# ultrasonic_rx.net
KiCad netlist of a schematic drawn in Altium Designer
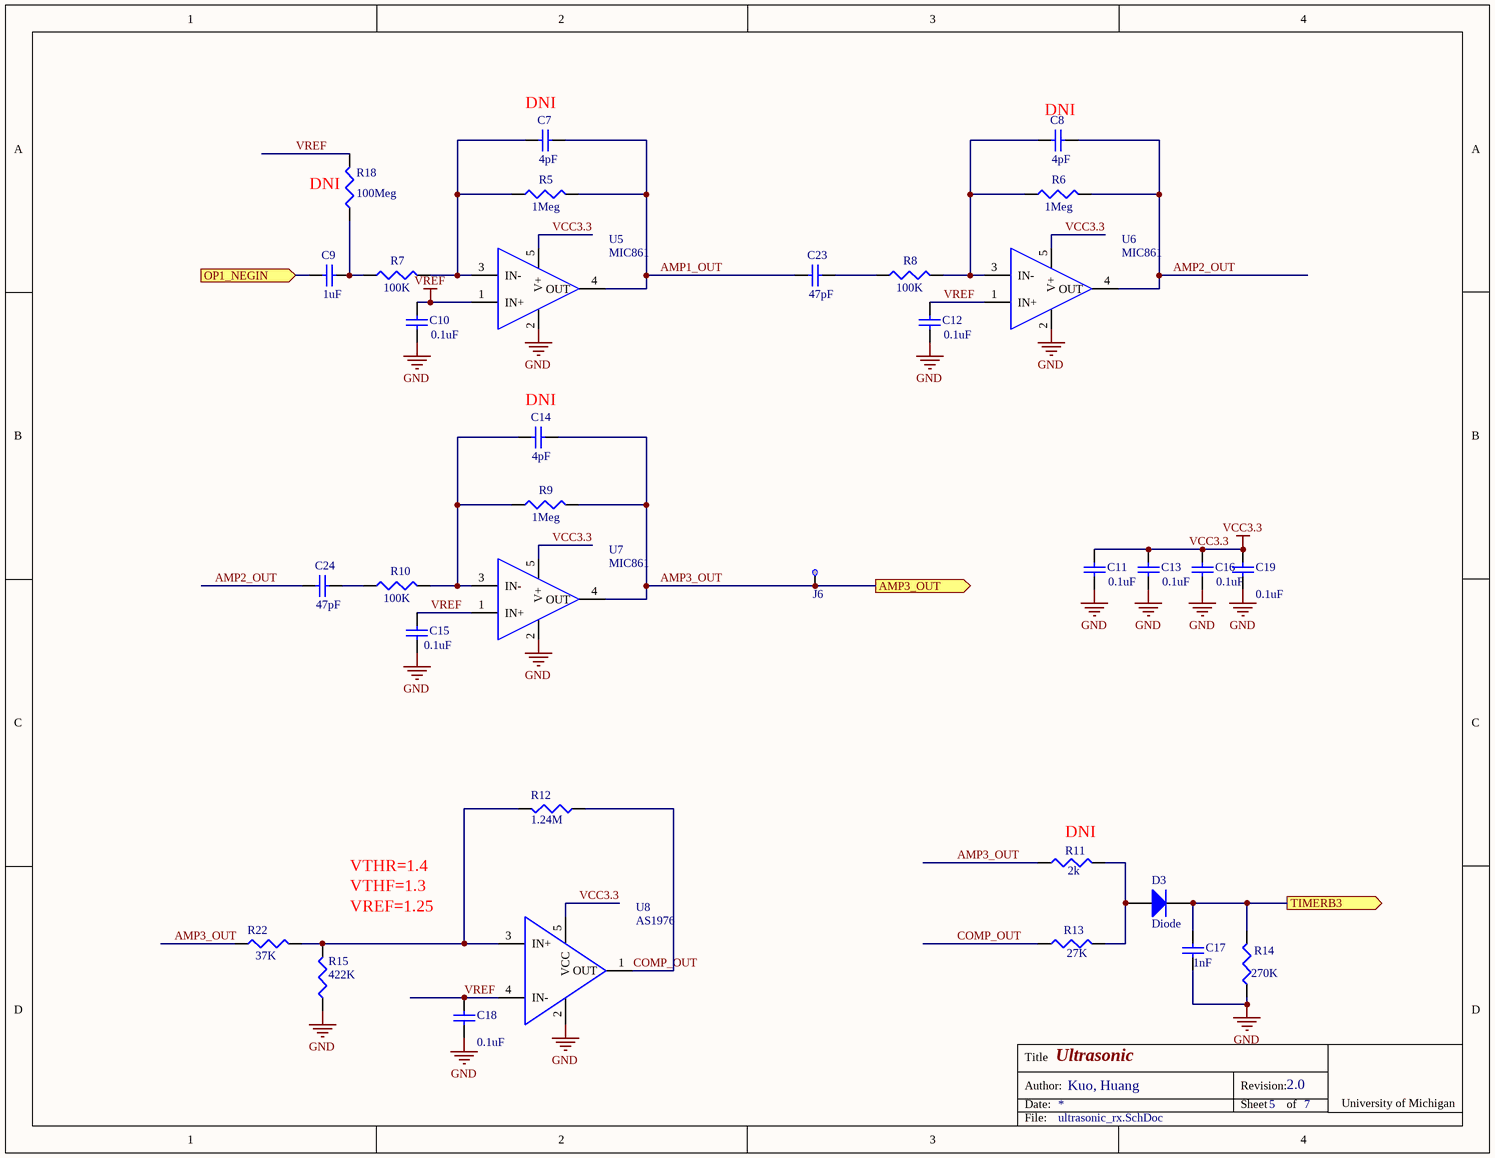
[diagram p0: ultrasonic_rx.SchDoc]

(export (version "E")
  (design (tool "Eeschema 10.0.6"))
  (components
    (comp (ref "C7")
      (value "4pF")
      (footprint "1608[0603]")
      (description "Capacitor (Semiconductor SIM Model)")
      (fields (field (name "Comment") "Cap Semi") (field (name "PUBLISHER") "Altium Limited"))
      (libsource (lib "Miscellaneous Devices") (part "Cap Semi"))
    )
    (comp (ref "C8")
      (value "4pF")
      (footprint "1608[0603]")
      (description "Capacitor (Semiconductor SIM Model)")
      (fields (field (name "Comment") "Cap Semi") (field (name "PUBLISHER") "Altium Limited"))
      (libsource (lib "Miscellaneous Devices") (part "Cap Semi"))
    )
    (comp (ref "C9")
      (value "1uF")
      (footprint "1608[0603]")
      (description "Capacitor (Semiconductor SIM Model)")
      (fields (field (name "Comment") "Cap Semi") (field (name "PUBLISHER") "Altium Limited"))
      (libsource (lib "Miscellaneous Devices") (part "Cap Semi"))
    )
    (comp (ref "C10")
      (value "0.1uF")
      (footprint "1608[0603]")
      (description "Capacitor (Semiconductor SIM Model)")
      (fields (field (name "Comment") "Cap Semi") (field (name "PUBLISHER") "Altium Limited"))
      (libsource (lib "Miscellaneous Devices") (part "Cap Semi"))
    )
    (comp (ref "C11")
      (value "0.1uF")
      (footprint "1608[0603]")
      (description "Capacitor (Semiconductor SIM Model)")
      (fields (field (name "Comment") "Cap Semi") (field (name "PUBLISHER") "Altium Limited"))
      (libsource (lib "Miscellaneous Devices") (part "Cap Semi"))
    )
    (comp (ref "C12")
      (value "0.1uF")
      (footprint "1608[0603]")
      (description "Capacitor (Semiconductor SIM Model)")
      (fields (field (name "Comment") "Cap Semi") (field (name "PUBLISHER") "Altium Limited"))
      (libsource (lib "Miscellaneous Devices") (part "Cap Semi"))
    )
    (comp (ref "C13")
      (value "0.1uF")
      (footprint "1608[0603]")
      (description "Capacitor (Semiconductor SIM Model)")
      (fields (field (name "Comment") "Cap Semi") (field (name "PUBLISHER") "Altium Limited"))
      (libsource (lib "Miscellaneous Devices") (part "Cap Semi"))
    )
    (comp (ref "C14")
      (value "4pF")
      (footprint "1608[0603]")
      (description "Capacitor (Semiconductor SIM Model)")
      (fields (field (name "Comment") "Cap Semi") (field (name "PUBLISHER") "Altium Limited"))
      (libsource (lib "Miscellaneous Devices") (part "Cap Semi"))
    )
    (comp (ref "C15")
      (value "0.1uF")
      (footprint "1608[0603]")
      (description "Capacitor (Semiconductor SIM Model)")
      (fields (field (name "Comment") "Cap Semi") (field (name "PUBLISHER") "Altium Limited"))
      (libsource (lib "Miscellaneous Devices") (part "Cap Semi"))
    )
    (comp (ref "C16")
      (value "0.1uF")
      (footprint "1608[0603]")
      (description "Capacitor (Semiconductor SIM Model)")
      (fields (field (name "Comment") "Cap Semi") (field (name "PUBLISHER") "Altium Limited"))
      (libsource (lib "Miscellaneous Devices") (part "Cap Semi"))
    )
    (comp (ref "C17")
      (value "1nF")
      (footprint "1608[0603]")
      (description "Capacitor (Semiconductor SIM Model)")
      (fields (field (name "Comment") "Cap Semi") (field (name "PUBLISHER") "Altium Limited"))
      (libsource (lib "Miscellaneous Devices") (part "Cap Semi"))
    )
    (comp (ref "C18")
      (value "0.1uF")
      (footprint "1608[0603]")
      (description "Capacitor (Semiconductor SIM Model)")
      (fields (field (name "Comment") "Cap Semi") (field (name "PUBLISHER") "Altium Limited"))
      (libsource (lib "Miscellaneous Devices") (part "Cap Semi"))
    )
    (comp (ref "C19")
      (value "0.1uF")
      (footprint "1608[0603]")
      (description "Capacitor (Semiconductor SIM Model)")
      (fields (field (name "Comment") "Cap Semi") (field (name "PUBLISHER") "Altium Limited"))
      (libsource (lib "Miscellaneous Devices") (part "Cap Semi"))
    )
    (comp (ref "C23")
      (value "47pF")
      (footprint "1608[0603]")
      (description "Capacitor (Semiconductor SIM Model)")
      (fields (field (name "Comment") "Cap Semi") (field (name "PUBLISHER") "Altium Limited"))
      (libsource (lib "Miscellaneous Devices") (part "Cap Semi"))
    )
    (comp (ref "C24")
      (value "47pF")
      (footprint "1608[0603]")
      (description "Capacitor (Semiconductor SIM Model)")
      (fields (field (name "Comment") "Cap Semi") (field (name "PUBLISHER") "Altium Limited"))
      (libsource (lib "Miscellaneous Devices") (part "Cap Semi"))
    )
    (comp (ref "D3")
      (value "Diode")
      (footprint "J1-0603")
      (description "Default Diode")
      (fields (field (name "PUBLISHER") "Altium Limited"))
      (libsource (lib "Miscellaneous Devices") (part "Diode"))
    )
    (comp (ref "J6")
      (value "5004")
      (footprint "TestPoint")
      (description "TEST POINT PC MINI .040\"D YELLOW")
      (libsource (lib "ultrasounic") (part "TestPoint"))
    )
    (comp (ref "R5")
      (value "1Meg")
      (footprint "J1-0603")
      (description "Resistor")
      (fields (field (name "PUBLISHER") "Altium Limited"))
      (libsource (lib "Miscellaneous Devices") (part "Res3"))
    )
    (comp (ref "R6")
      (value "1Meg")
      (footprint "J1-0603")
      (description "Resistor")
      (fields (field (name "PUBLISHER") "Altium Limited"))
      (libsource (lib "Miscellaneous Devices") (part "Res3"))
    )
    (comp (ref "R7")
      (value "100K")
      (footprint "J1-0603")
      (description "Resistor")
      (fields (field (name "PUBLISHER") "Altium Limited"))
      (libsource (lib "Miscellaneous Devices") (part "Res3"))
    )
    (comp (ref "R8")
      (value "100K")
      (footprint "J1-0603")
      (description "Resistor")
      (fields (field (name "PUBLISHER") "Altium Limited"))
      (libsource (lib "Miscellaneous Devices") (part "Res3"))
    )
    (comp (ref "R9")
      (value "1Meg")
      (footprint "J1-0603")
      (description "Resistor")
      (fields (field (name "PUBLISHER") "Altium Limited"))
      (libsource (lib "Miscellaneous Devices") (part "Res3"))
    )
    (comp (ref "R10")
      (value "100K")
      (footprint "J1-0603")
      (description "Resistor")
      (fields (field (name "PUBLISHER") "Altium Limited"))
      (libsource (lib "Miscellaneous Devices") (part "Res3"))
    )
    (comp (ref "R11")
      (value "2k")
      (footprint "J1-0603")
      (description "Resistor")
      (fields (field (name "PUBLISHER") "Altium Limited"))
      (libsource (lib "Miscellaneous Devices") (part "Res3"))
    )
    (comp (ref "R12")
      (value "1.24M")
      (footprint "J1-0603")
      (description "Resistor")
      (fields (field (name "PUBLISHER") "Altium Limited"))
      (libsource (lib "Miscellaneous Devices") (part "Res3"))
    )
    (comp (ref "R13")
      (value "27K")
      (footprint "J1-0603")
      (description "Resistor")
      (fields (field (name "PUBLISHER") "Altium Limited"))
      (libsource (lib "Miscellaneous Devices") (part "Res3"))
    )
    (comp (ref "R14")
      (value "270K")
      (footprint "J1-0603")
      (description "Resistor")
      (fields (field (name "PUBLISHER") "Altium Limited"))
      (libsource (lib "Miscellaneous Devices") (part "Res3"))
    )
    (comp (ref "R15")
      (value "422K")
      (footprint "J1-0603")
      (description "Resistor")
      (fields (field (name "PUBLISHER") "Altium Limited"))
      (libsource (lib "Miscellaneous Devices") (part "Res3"))
    )
    (comp (ref "R18")
      (value "100Meg")
      (footprint "J1-0603")
      (description "Resistor")
      (fields (field (name "Comment") "Res3") (field (name "PUBLISHER") "Altium Limited"))
      (libsource (lib "Miscellaneous Devices") (part "Res3"))
    )
    (comp (ref "R22")
      (value "37K")
      (footprint "J1-0603")
      (description "Resistor")
      (fields (field (name "Comment") "27K") (field (name "PUBLISHER") "Altium Limited"))
      (libsource (lib "Miscellaneous Devices") (part "Res3"))
    )
    (comp (ref "U5")
      (value "MIC861")
      (footprint "SC70-5")
      (description "IC OPAMP 400KHZ 2.7V ULT LP SC70")
      (libsource (lib "ultrasounic") (part "MIC861"))
    )
    (comp (ref "U6")
      (value "MIC861")
      (footprint "SC70-5")
      (description "IC OPAMP 400KHZ 2.7V ULT LP SC70")
      (libsource (lib "ultrasounic") (part "MIC861"))
    )
    (comp (ref "U7")
      (value "MIC861")
      (footprint "SC70-5")
      (description "IC OPAMP 400KHZ 2.7V ULT LP SC70")
      (libsource (lib "ultrasounic") (part "MIC861"))
    )
    (comp (ref "U8")
      (value "AS1976")
      (footprint "SOT23-5")
      (description "IC COMPARATOR PUSH/PULL SOT23-5")
      (libsource (lib "ultrasounic") (part "AS1976"))
    )
  )
  (nets
    (net (code "1") (name "/AMP1_OUT") (class "Default")
      (node (ref "C23") (pin "1") (pinfunction "1_1") (pintype "passive"))
      (node (ref "C7") (pin "1") (pinfunction "1_1") (pintype "passive"))
      (node (ref "R5") (pin "2") (pinfunction "2_2") (pintype "passive"))
      (node (ref "U5") (pin "4") (pinfunction "OUT_4") (pintype "passive"))
    )
    (net (code "2") (name "/AMP2_OUT") (class "Default")
      (node (ref "C24") (pin "1") (pinfunction "1_1") (pintype "passive"))
      (node (ref "C8") (pin "1") (pinfunction "1_1") (pintype "passive"))
      (node (ref "R6") (pin "2") (pinfunction "2_2") (pintype "passive"))
      (node (ref "U6") (pin "4") (pinfunction "OUT_4") (pintype "passive"))
    )
    (net (code "3") (name "/AMP3_OUT") (class "Default")
      (node (ref "C14") (pin "1") (pinfunction "1_1") (pintype "passive"))
      (node (ref "J6") (pin "1") (pinfunction "TB_1") (pintype "passive"))
      (node (ref "R11") (pin "1") (pinfunction "1_1") (pintype "passive"))
      (node (ref "R22") (pin "1") (pinfunction "1_1") (pintype "passive"))
      (node (ref "R9") (pin "2") (pinfunction "2_2") (pintype "passive"))
      (node (ref "U7") (pin "4") (pinfunction "OUT_4") (pintype "passive"))
    )
    (net (code "4") (name "/COMP_OUT") (class "Default")
      (node (ref "R12") (pin "1") (pinfunction "1_1") (pintype "passive"))
      (node (ref "R13") (pin "1") (pinfunction "1_1") (pintype "passive"))
      (node (ref "U8") (pin "1") (pinfunction "OUT_1") (pintype "passive"))
    )
    (net (code "5") (name "/OP1_NEGIN") (class "Default")
      (node (ref "C9") (pin "2") (pinfunction "2_2") (pintype "passive"))
    )
    (net (code "6") (name "/TIMERB3") (class "Default")
      (node (ref "C17") (pin "1") (pinfunction "1_1") (pintype "passive"))
      (node (ref "D3") (pin "2") (pinfunction "K_2") (pintype "passive"))
      (node (ref "R14") (pin "2") (pinfunction "2_2") (pintype "passive"))
    )
    (net (code "7") (name "GND") (class "Default")
      (node (ref "C10") (pin "1") (pinfunction "1_1") (pintype "passive"))
      (node (ref "C11") (pin "1") (pinfunction "1_1") (pintype "passive"))
      (node (ref "C12") (pin "1") (pinfunction "1_1") (pintype "passive"))
      (node (ref "C13") (pin "1") (pinfunction "1_1") (pintype "passive"))
      (node (ref "C15") (pin "1") (pinfunction "1_1") (pintype "passive"))
      (node (ref "C16") (pin "1") (pinfunction "1_1") (pintype "passive"))
      (node (ref "C17") (pin "2") (pinfunction "2_2") (pintype "passive"))
      (node (ref "C18") (pin "1") (pinfunction "1_1") (pintype "passive"))
      (node (ref "C19") (pin "1") (pinfunction "1_1") (pintype "passive"))
      (node (ref "R14") (pin "1") (pinfunction "1_1") (pintype "passive"))
      (node (ref "R15") (pin "1") (pinfunction "1_1") (pintype "passive"))
      (node (ref "U5") (pin "2") (pinfunction "V-_2") (pintype "passive"))
      (node (ref "U6") (pin "2") (pinfunction "V-_2") (pintype "passive"))
      (node (ref "U7") (pin "2") (pinfunction "V-_2") (pintype "passive"))
      (node (ref "U8") (pin "2") (pinfunction "VEE_2") (pintype "passive"))
    )
    (net (code "8") (name "Net-(C9-Pad1)") (class "Default")
      (node (ref "C9") (pin "1") (pinfunction "1_1") (pintype "passive"))
      (node (ref "R18") (pin "1") (pinfunction "1_1") (pintype "passive"))
      (node (ref "R7") (pin "1") (pinfunction "1_1") (pintype "passive"))
    )
    (net (code "9") (name "Net-(C23-Pad2)") (class "Default")
      (node (ref "C23") (pin "2") (pinfunction "2_2") (pintype "passive"))
      (node (ref "R8") (pin "1") (pinfunction "1_1") (pintype "passive"))
    )
    (net (code "10") (name "Net-(C24-Pad2)") (class "Default")
      (node (ref "C24") (pin "2") (pinfunction "2_2") (pintype "passive"))
      (node (ref "R10") (pin "1") (pinfunction "1_1") (pintype "passive"))
    )
    (net (code "11") (name "Net-(D3-A)") (class "Default")
      (node (ref "D3") (pin "1") (pinfunction "A_1") (pintype "passive"))
      (node (ref "R11") (pin "2") (pinfunction "2_2") (pintype "passive"))
      (node (ref "R13") (pin "2") (pinfunction "2_2") (pintype "passive"))
    )
    (net (code "12") (name "Net-(U5-IN-)") (class "Default")
      (node (ref "C7") (pin "2") (pinfunction "2_2") (pintype "passive"))
      (node (ref "R5") (pin "1") (pinfunction "1_1") (pintype "passive"))
      (node (ref "R7") (pin "2") (pinfunction "2_2") (pintype "passive"))
      (node (ref "U5") (pin "3") (pinfunction "IN-_3") (pintype "passive"))
    )
    (net (code "13") (name "Net-(U6-IN-)") (class "Default")
      (node (ref "C8") (pin "2") (pinfunction "2_2") (pintype "passive"))
      (node (ref "R6") (pin "1") (pinfunction "1_1") (pintype "passive"))
      (node (ref "R8") (pin "2") (pinfunction "2_2") (pintype "passive"))
      (node (ref "U6") (pin "3") (pinfunction "IN-_3") (pintype "passive"))
    )
    (net (code "14") (name "Net-(U7-IN-)") (class "Default")
      (node (ref "C14") (pin "2") (pinfunction "2_2") (pintype "passive"))
      (node (ref "R10") (pin "2") (pinfunction "2_2") (pintype "passive"))
      (node (ref "R9") (pin "1") (pinfunction "1_1") (pintype "passive"))
      (node (ref "U7") (pin "3") (pinfunction "IN-_3") (pintype "passive"))
    )
    (net (code "15") (name "Net-(U8-IN+)") (class "Default")
      (node (ref "R12") (pin "2") (pinfunction "2_2") (pintype "passive"))
      (node (ref "R15") (pin "2") (pinfunction "2_2") (pintype "passive"))
      (node (ref "R22") (pin "2") (pinfunction "2_2") (pintype "passive"))
      (node (ref "U8") (pin "3") (pinfunction "IN+_3") (pintype "passive"))
    )
    (net (code "16") (name "VCC3.3") (class "Default")
      (node (ref "C11") (pin "2") (pinfunction "2_2") (pintype "passive"))
      (node (ref "C13") (pin "2") (pinfunction "2_2") (pintype "passive"))
      (node (ref "C16") (pin "2") (pinfunction "2_2") (pintype "passive"))
      (node (ref "C19") (pin "2") (pinfunction "2_2") (pintype "passive"))
      (node (ref "U5") (pin "5") (pinfunction "V+_5") (pintype "passive"))
      (node (ref "U6") (pin "5") (pinfunction "V+_5") (pintype "passive"))
      (node (ref "U7") (pin "5") (pinfunction "V+_5") (pintype "passive"))
      (node (ref "U8") (pin "5") (pinfunction "VCC_5") (pintype "passive"))
    )
    (net (code "17") (name "VREF") (class "Default")
      (node (ref "C10") (pin "2") (pinfunction "2_2") (pintype "passive"))
      (node (ref "C12") (pin "2") (pinfunction "2_2") (pintype "passive"))
      (node (ref "C15") (pin "2") (pinfunction "2_2") (pintype "passive"))
      (node (ref "C18") (pin "2") (pinfunction "2_2") (pintype "passive"))
      (node (ref "R18") (pin "2") (pinfunction "2_2") (pintype "passive"))
      (node (ref "U5") (pin "1") (pinfunction "IN+_1") (pintype "passive"))
      (node (ref "U6") (pin "1") (pinfunction "IN+_1") (pintype "passive"))
      (node (ref "U7") (pin "1") (pinfunction "IN+_1") (pintype "passive"))
      (node (ref "U8") (pin "4") (pinfunction "IN-_4") (pintype "passive"))
    )
  )
)
